# Sat_Cape_v9.net
KiCad netlist of a schematic drawn in EAGLE
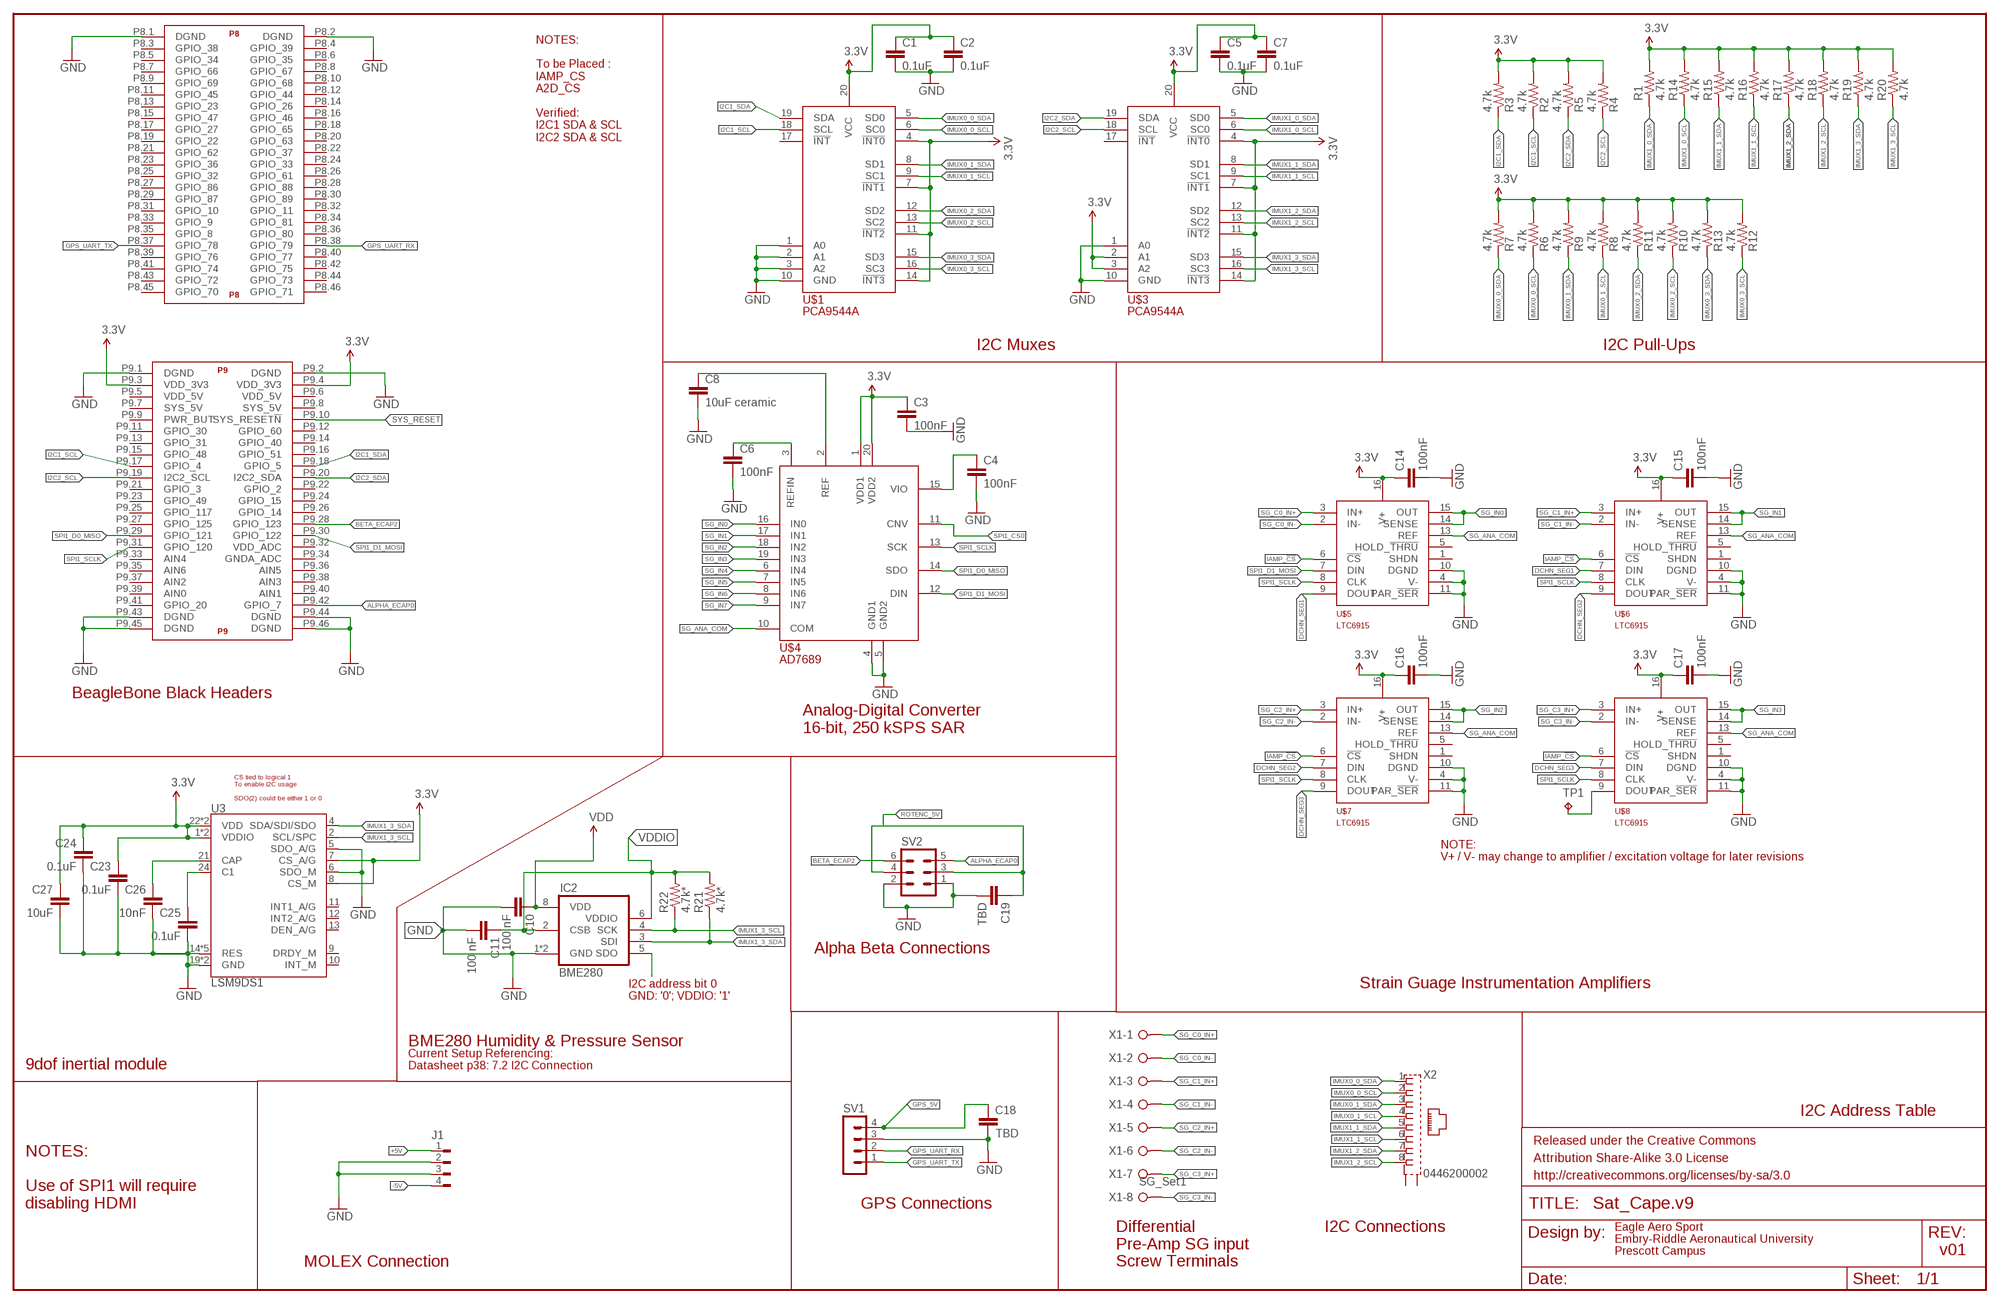
[diagram p0: schematic, sheet 1]

(export (version "E")
  (design (tool "Eeschema 10.0.6"))
  (components
    (comp (ref "C1")
      (value "0.1uF")
      (footprint "eagle-import:0805")
      (libsource (lib "eagle-import") (part "CAP0805"))
    )
    (comp (ref "C2")
      (value "0.1uF")
      (footprint "eagle-import:0805")
      (libsource (lib "eagle-import") (part "CAP0805"))
    )
    (comp (ref "C3")
      (value "100nF")
      (footprint "eagle-import:0805")
      (libsource (lib "eagle-import") (part "CAP0805"))
    )
    (comp (ref "C4")
      (value "100nF")
      (footprint "eagle-import:0805")
      (libsource (lib "eagle-import") (part "CAP0805"))
    )
    (comp (ref "C5")
      (value "0.1uF")
      (footprint "eagle-import:0805")
      (libsource (lib "eagle-import") (part "CAP0805"))
    )
    (comp (ref "C6")
      (value "100nF")
      (footprint "eagle-import:0805")
      (libsource (lib "eagle-import") (part "CAP0805"))
    )
    (comp (ref "C7")
      (value "0.1uF")
      (footprint "eagle-import:0805")
      (libsource (lib "eagle-import") (part "CAP0805"))
    )
    (comp (ref "C8")
      (value "10uF ceramic")
      (footprint "eagle-import:0805")
      (libsource (lib "eagle-import") (part "CAP0805"))
    )
    (comp (ref "C10")
      (value "100 nF")
      (footprint "eagle-import:0805")
      (libsource (lib "eagle-import") (part "CAP0805"))
    )
    (comp (ref "C11")
      (value "100 nF")
      (footprint "eagle-import:0805")
      (libsource (lib "eagle-import") (part "CAP0805"))
    )
    (comp (ref "C14")
      (value "100nF")
      (footprint "eagle-import:0805")
      (libsource (lib "eagle-import") (part "CAP0805"))
    )
    (comp (ref "C15")
      (value "100nF")
      (footprint "eagle-import:0805")
      (libsource (lib "eagle-import") (part "CAP0805"))
    )
    (comp (ref "C16")
      (value "100nF")
      (footprint "eagle-import:0805")
      (libsource (lib "eagle-import") (part "CAP0805"))
    )
    (comp (ref "C17")
      (value "100nF")
      (footprint "eagle-import:0805")
      (libsource (lib "eagle-import") (part "CAP0805"))
    )
    (comp (ref "C18")
      (value "TBD")
      (footprint "eagle-import:0805")
      (libsource (lib "eagle-import") (part "CAP0805"))
    )
    (comp (ref "C19")
      (value "TBD")
      (footprint "eagle-import:0805")
      (libsource (lib "eagle-import") (part "CAP0805"))
    )
    (comp (ref "C23")
      (value "0.1uF")
      (footprint "eagle-import:0805")
      (libsource (lib "eagle-import") (part "CAP0805"))
    )
    (comp (ref "C24")
      (value "0.1uF")
      (footprint "eagle-import:0805")
      (libsource (lib "eagle-import") (part "CAP0805"))
    )
    (comp (ref "C25")
      (value "0.1uF")
      (footprint "eagle-import:0805")
      (libsource (lib "eagle-import") (part "CAP0805"))
    )
    (comp (ref "C26")
      (value "10nF")
      (footprint "eagle-import:0805")
      (libsource (lib "eagle-import") (part "CAP0805"))
    )
    (comp (ref "C27")
      (value "10uF")
      (footprint "eagle-import:0805")
      (libsource (lib "eagle-import") (part "CAP0805"))
    )
    (comp (ref "FRAME1")
      (value "FRAME-LEDGER")
      (footprint "eagle-import:CREATIVE_COMMONS")
      (libsource (lib "eagle-import") (part "FRAME-LEDGER"))
    )
    (comp (ref "IC2")
      (value "BME280")
      (footprint "eagle-import:BME280")
      (libsource (lib "eagle-import") (part "BME280"))
    )
    (comp (ref "J1")
      (value "FLOPPY-4350211")
      (footprint "eagle-import:350211")
      (libsource (lib "eagle-import") (part "FLOPPY-4350211"))
    )
    (comp (ref "R1")
      (value "4.7k")
      (footprint "eagle-import:0805")
      (libsource (lib "eagle-import") (part "RESISTOR0805-RES"))
    )
    (comp (ref "R2")
      (value "4.7k")
      (footprint "eagle-import:0805")
      (libsource (lib "eagle-import") (part "RESISTOR0805-RES"))
    )
    (comp (ref "R3")
      (value "4.7k")
      (footprint "eagle-import:0805")
      (libsource (lib "eagle-import") (part "RESISTOR0805-RES"))
    )
    (comp (ref "R4")
      (value "4.7k")
      (footprint "eagle-import:0805")
      (libsource (lib "eagle-import") (part "RESISTOR0805-RES"))
    )
    (comp (ref "R5")
      (value "4.7k")
      (footprint "eagle-import:0805")
      (libsource (lib "eagle-import") (part "RESISTOR0805-RES"))
    )
    (comp (ref "R6")
      (value "4.7k")
      (footprint "eagle-import:0805")
      (libsource (lib "eagle-import") (part "RESISTOR0805-RES"))
    )
    (comp (ref "R7")
      (value "4.7k")
      (footprint "eagle-import:0805")
      (libsource (lib "eagle-import") (part "RESISTOR0805-RES"))
    )
    (comp (ref "R8")
      (value "4.7k")
      (footprint "eagle-import:0805")
      (libsource (lib "eagle-import") (part "RESISTOR0805-RES"))
    )
    (comp (ref "R9")
      (value "4.7k")
      (footprint "eagle-import:0805")
      (libsource (lib "eagle-import") (part "RESISTOR0805-RES"))
    )
    (comp (ref "R10")
      (value "4.7k")
      (footprint "eagle-import:0805")
      (libsource (lib "eagle-import") (part "RESISTOR0805-RES"))
    )
    (comp (ref "R11")
      (value "4.7k")
      (footprint "eagle-import:0805")
      (libsource (lib "eagle-import") (part "RESISTOR0805-RES"))
    )
    (comp (ref "R12")
      (value "4.7k")
      (footprint "eagle-import:0805")
      (libsource (lib "eagle-import") (part "RESISTOR0805-RES"))
    )
    (comp (ref "R13")
      (value "4.7k")
      (footprint "eagle-import:0805")
      (libsource (lib "eagle-import") (part "RESISTOR0805-RES"))
    )
    (comp (ref "R14")
      (value "4.7k")
      (footprint "eagle-import:0805")
      (libsource (lib "eagle-import") (part "RESISTOR0805-RES"))
    )
    (comp (ref "R15")
      (value "4.7k")
      (footprint "eagle-import:0805")
      (libsource (lib "eagle-import") (part "RESISTOR0805-RES"))
    )
    (comp (ref "R16")
      (value "4.7k")
      (footprint "eagle-import:0805")
      (libsource (lib "eagle-import") (part "RESISTOR0805-RES"))
    )
    (comp (ref "R17")
      (value "4.7k")
      (footprint "eagle-import:0805")
      (libsource (lib "eagle-import") (part "RESISTOR0805-RES"))
    )
    (comp (ref "R18")
      (value "4.7k")
      (footprint "eagle-import:0805")
      (libsource (lib "eagle-import") (part "RESISTOR0805-RES"))
    )
    (comp (ref "R19")
      (value "4.7k")
      (footprint "eagle-import:0805")
      (libsource (lib "eagle-import") (part "RESISTOR0805-RES"))
    )
    (comp (ref "R20")
      (value "4.7k")
      (footprint "eagle-import:0805")
      (libsource (lib "eagle-import") (part "RESISTOR0805-RES"))
    )
    (comp (ref "R21")
      (value "4.7k*")
      (footprint "eagle-import:0805")
      (libsource (lib "eagle-import") (part "RESISTOR0805-RES"))
    )
    (comp (ref "R22")
      (value "4.7k*")
      (footprint "eagle-import:0805")
      (libsource (lib "eagle-import") (part "RESISTOR0805-RES"))
    )
    (comp (ref "SV1")
      (value "MA04-1")
      (footprint "eagle-import:MA04-1")
      (libsource (lib "eagle-import") (part "MA04-1"))
    )
    (comp (ref "SV2")
      (value "MA03-2")
      (footprint "eagle-import:MA03-2")
      (libsource (lib "eagle-import") (part "MA03-2"))
    )
    (comp (ref "TP1")
      (value "TPTP08R")
      (footprint "eagle-import:TP08R")
      (libsource (lib "eagle-import") (part "TPTP08R"))
    )
    (comp (ref "U$1")
      (value "PCA9544A")
      (footprint "eagle-import:TSSOP20")
      (libsource (lib "eagle-import") (part "PCA9544A"))
    )
    (comp (ref "U$2")
      (value "BEAGLE_BONE_BLACK_CAPE")
      (footprint "eagle-import:BEAGLE_BONE_BLACK_CAPE")
      (libsource (lib "eagle-import") (part "BEAGLE_BONE_BLACK_CAPE"))
    )
    (comp (ref "U$3")
      (value "PCA9544A")
      (footprint "eagle-import:TSSOP20")
      (libsource (lib "eagle-import") (part "PCA9544A"))
    )
    (comp (ref "U$4")
      (value "AD7689")
      (footprint "eagle-import:QFN20")
      (libsource (lib "eagle-import") (part "AD7689"))
    )
    (comp (ref "U$5")
      (value "LTC6915")
      (footprint "eagle-import:SSOP16")
      (libsource (lib "eagle-import") (part "LTC6915"))
    )
    (comp (ref "U$6")
      (value "LTC6915")
      (footprint "eagle-import:SSOP16")
      (libsource (lib "eagle-import") (part "LTC6915"))
    )
    (comp (ref "U$7")
      (value "LTC6915")
      (footprint "eagle-import:SSOP16")
      (libsource (lib "eagle-import") (part "LTC6915"))
    )
    (comp (ref "U$8")
      (value "LTC6915")
      (footprint "eagle-import:SSOP16")
      (libsource (lib "eagle-import") (part "LTC6915"))
    )
    (comp (ref "U3")
      (value "LSM9DS1")
      (footprint "eagle-import:LGA24-8X4")
      (libsource (lib "eagle-import") (part "LSM9DS1"))
    )
    (comp (ref "X1")
      (value "SG_Set1")
      (footprint "eagle-import:W237-8P")
      (libsource (lib "eagle-import") (part "W237-08P"))
    )
    (comp (ref "X2")
      (value "0446200002")
      (footprint "eagle-import:0446200002")
      (fields (field (name "MF") "MOLEX"))
      (libsource (lib "eagle-import") (part "0446200002"))
    )
  )
  (nets
    (net (code "1") (name "+5V") (class "Default")
      (node (ref "J1") (pin "1") (pinfunction "1_1") (pintype "passive"))
    )
    (net (code "2") (name "-5V") (class "Default")
      (node (ref "J1") (pin "4") (pinfunction "4_4") (pintype "passive"))
    )
    (net (code "3") (name "/IAMP_~{CS}") (class "Default")
      (node (ref "U$5") (pin "6") (pinfunction "~{CS}_6") (pintype "bidirectional"))
      (node (ref "U$6") (pin "6") (pinfunction "~{CS}_6") (pintype "bidirectional"))
      (node (ref "U$7") (pin "6") (pinfunction "~{CS}_6") (pintype "bidirectional"))
      (node (ref "U$8") (pin "6") (pinfunction "~{CS}_6") (pintype "bidirectional"))
    )
    (net (code "4") (name "3.3V") (class "Default")
      (node (ref "C1") (pin "1") (pinfunction "1_1") (pintype "passive"))
      (node (ref "C14") (pin "1") (pinfunction "1_1") (pintype "passive"))
      (node (ref "C15") (pin "1") (pinfunction "1_1") (pintype "passive"))
      (node (ref "C16") (pin "1") (pinfunction "1_1") (pintype "passive"))
      (node (ref "C17") (pin "1") (pinfunction "1_1") (pintype "passive"))
      (node (ref "C2") (pin "1") (pinfunction "1_1") (pintype "passive"))
      (node (ref "C23") (pin "1") (pinfunction "1_1") (pintype "passive"))
      (node (ref "C24") (pin "1") (pinfunction "1_1") (pintype "passive"))
      (node (ref "C27") (pin "1") (pinfunction "1_1") (pintype "passive"))
      (node (ref "C3") (pin "1") (pinfunction "1_1") (pintype "passive"))
      (node (ref "C5") (pin "1") (pinfunction "1_1") (pintype "passive"))
      (node (ref "C7") (pin "1") (pinfunction "1_1") (pintype "passive"))
      (node (ref "R1") (pin "2") (pinfunction "2_2") (pintype "passive"))
      (node (ref "R10") (pin "2") (pinfunction "2_2") (pintype "passive"))
      (node (ref "R11") (pin "2") (pinfunction "2_2") (pintype "passive"))
      (node (ref "R12") (pin "2") (pinfunction "2_2") (pintype "passive"))
      (node (ref "R13") (pin "2") (pinfunction "2_2") (pintype "passive"))
      (node (ref "R14") (pin "2") (pinfunction "2_2") (pintype "passive"))
      (node (ref "R15") (pin "2") (pinfunction "2_2") (pintype "passive"))
      (node (ref "R16") (pin "2") (pinfunction "2_2") (pintype "passive"))
      (node (ref "R17") (pin "2") (pinfunction "2_2") (pintype "passive"))
      (node (ref "R18") (pin "2") (pinfunction "2_2") (pintype "passive"))
      (node (ref "R19") (pin "2") (pinfunction "2_2") (pintype "passive"))
      (node (ref "R2") (pin "2") (pinfunction "2_2") (pintype "passive"))
      (node (ref "R20") (pin "2") (pinfunction "2_2") (pintype "passive"))
      (node (ref "R3") (pin "2") (pinfunction "2_2") (pintype "passive"))
      (node (ref "R4") (pin "2") (pinfunction "2_2") (pintype "passive"))
      (node (ref "R5") (pin "2") (pinfunction "2_2") (pintype "passive"))
      (node (ref "R6") (pin "2") (pinfunction "2_2") (pintype "passive"))
      (node (ref "R7") (pin "2") (pinfunction "2_2") (pintype "passive"))
      (node (ref "R8") (pin "2") (pinfunction "2_2") (pintype "passive"))
      (node (ref "R9") (pin "2") (pinfunction "2_2") (pintype "passive"))
      (node (ref "U$1") (pin "11") (pinfunction "~{INT2}_11") (pintype "input"))
      (node (ref "U$1") (pin "14") (pinfunction "~{INT3}_14") (pintype "input"))
      (node (ref "U$1") (pin "20") (pinfunction "VCC_20") (pintype "power_in"))
      (node (ref "U$1") (pin "4") (pinfunction "~{INT0}_4") (pintype "input"))
      (node (ref "U$1") (pin "7") (pinfunction "~{INT1}_7") (pintype "input"))
      (node (ref "U$2") (pin "P9.3") (pinfunction "VDD_3V3_P9.3") (pintype "bidirectional"))
      (node (ref "U$2") (pin "P9.4") (pinfunction "VDD_3V3_P9.4") (pintype "bidirectional"))
      (node (ref "U$3") (pin "11") (pinfunction "~{INT2}_11") (pintype "input"))
      (node (ref "U$3") (pin "14") (pinfunction "~{INT3}_14") (pintype "input"))
      (node (ref "U$3") (pin "2") (pinfunction "A1_2") (pintype "input"))
      (node (ref "U$3") (pin "20") (pinfunction "VCC_20") (pintype "power_in"))
      (node (ref "U$3") (pin "3") (pinfunction "A2_3") (pintype "input"))
      (node (ref "U$3") (pin "4") (pinfunction "~{INT0}_4") (pintype "input"))
      (node (ref "U$3") (pin "7") (pinfunction "~{INT1}_7") (pintype "input"))
      (node (ref "U$4") (pin "1") (pinfunction "VDD1_1") (pintype "bidirectional"))
      (node (ref "U$4") (pin "20") (pinfunction "VDD2_20") (pintype "bidirectional"))
      (node (ref "U$5") (pin "16") (pinfunction "V+_16") (pintype "bidirectional"))
      (node (ref "U$6") (pin "16") (pinfunction "V+_16") (pintype "bidirectional"))
      (node (ref "U$7") (pin "16") (pinfunction "V+_16") (pintype "bidirectional"))
      (node (ref "U$8") (pin "16") (pinfunction "V+_16") (pintype "bidirectional"))
      (node (ref "U3") (pin "1") (pinfunction "VDDIO_1") (pintype "bidirectional"))
      (node (ref "U3") (pin "22") (pinfunction "VDD_22") (pintype "bidirectional"))
      (node (ref "U3") (pin "23") (pinfunction "VDD_23") (pintype "bidirectional"))
      (node (ref "U3") (pin "3") (pinfunction "VDDIO_3") (pintype "bidirectional"))
      (node (ref "U3") (pin "7") (pinfunction "CS_A/G_7") (pintype "bidirectional"))
      (node (ref "U3") (pin "8") (pinfunction "CS_M_8") (pintype "bidirectional"))
    )
    (net (code "5") (name "ALPHA_ECAP0") (class "Default")
      (node (ref "SV2") (pin "5") (pinfunction "5_5") (pintype "passive"))
      (node (ref "U$2") (pin "P9.42") (pinfunction "GPIO_7_P9.42") (pintype "bidirectional"))
    )
    (net (code "6") (name "BETA_ECAP2") (class "Default")
      (node (ref "SV2") (pin "6") (pinfunction "6_6") (pintype "passive"))
      (node (ref "U$2") (pin "P9.28") (pinfunction "GPIO_123_P9.28") (pintype "bidirectional"))
    )
    (net (code "7") (name "DCHN_SEG1") (class "Default")
      (node (ref "U$5") (pin "9") (pinfunction "DOUT_9") (pintype "bidirectional"))
      (node (ref "U$6") (pin "7") (pinfunction "DIN_7") (pintype "bidirectional"))
    )
    (net (code "8") (name "DCHN_SEG2") (class "Default")
      (node (ref "U$6") (pin "9") (pinfunction "DOUT_9") (pintype "bidirectional"))
      (node (ref "U$7") (pin "7") (pinfunction "DIN_7") (pintype "bidirectional"))
    )
    (net (code "9") (name "DCHN_SEG3") (class "Default")
      (node (ref "U$7") (pin "9") (pinfunction "DOUT_9") (pintype "bidirectional"))
      (node (ref "U$8") (pin "7") (pinfunction "DIN_7") (pintype "bidirectional"))
    )
    (net (code "10") (name "GND") (class "Default")
      (node (ref "C1") (pin "2") (pinfunction "2_2") (pintype "passive"))
      (node (ref "C10") (pin "2") (pinfunction "2_2") (pintype "passive"))
      (node (ref "C11") (pin "2") (pinfunction "2_2") (pintype "passive"))
      (node (ref "C14") (pin "2") (pinfunction "2_2") (pintype "passive"))
      (node (ref "C15") (pin "2") (pinfunction "2_2") (pintype "passive"))
      (node (ref "C16") (pin "2") (pinfunction "2_2") (pintype "passive"))
      (node (ref "C17") (pin "2") (pinfunction "2_2") (pintype "passive"))
      (node (ref "C18") (pin "2") (pinfunction "2_2") (pintype "passive"))
      (node (ref "C19") (pin "2") (pinfunction "2_2") (pintype "passive"))
      (node (ref "C2") (pin "2") (pinfunction "2_2") (pintype "passive"))
      (node (ref "C23") (pin "2") (pinfunction "2_2") (pintype "passive"))
      (node (ref "C24") (pin "2") (pinfunction "2_2") (pintype "passive"))
      (node (ref "C25") (pin "2") (pinfunction "2_2") (pintype "passive"))
      (node (ref "C26") (pin "2") (pinfunction "2_2") (pintype "passive"))
      (node (ref "C27") (pin "2") (pinfunction "2_2") (pintype "passive"))
      (node (ref "C3") (pin "2") (pinfunction "2_2") (pintype "passive"))
      (node (ref "C4") (pin "2") (pinfunction "2_2") (pintype "passive"))
      (node (ref "C5") (pin "2") (pinfunction "2_2") (pintype "passive"))
      (node (ref "C6") (pin "2") (pinfunction "2_2") (pintype "passive"))
      (node (ref "C7") (pin "2") (pinfunction "2_2") (pintype "passive"))
      (node (ref "C8") (pin "2") (pinfunction "2_2") (pintype "passive"))
      (node (ref "IC2") (pin "1") (pinfunction "GND_1") (pintype "power_in"))
      (node (ref "IC2") (pin "7") (pinfunction "GND_7") (pintype "power_in"))
      (node (ref "J1") (pin "2") (pinfunction "2_2") (pintype "passive"))
      (node (ref "J1") (pin "3") (pinfunction "3_3") (pintype "passive"))
      (node (ref "SV1") (pin "3") (pinfunction "3_3") (pintype "passive"))
      (node (ref "SV2") (pin "1") (pinfunction "1_1") (pintype "passive"))
      (node (ref "SV2") (pin "2") (pinfunction "2_2") (pintype "passive"))
      (node (ref "U$1") (pin "1") (pinfunction "A0_1") (pintype "input"))
      (node (ref "U$1") (pin "10") (pinfunction "GND_10") (pintype "power_in"))
      (node (ref "U$1") (pin "2") (pinfunction "A1_2") (pintype "input"))
      (node (ref "U$1") (pin "3") (pinfunction "A2_3") (pintype "input"))
      (node (ref "U$2") (pin "P8.1") (pinfunction "DGND_P8.1") (pintype "bidirectional"))
      (node (ref "U$2") (pin "P8.2") (pinfunction "DGND_P8.2") (pintype "bidirectional"))
      (node (ref "U$2") (pin "P9.1") (pinfunction "DGND_P9.1") (pintype "bidirectional"))
      (node (ref "U$2") (pin "P9.2") (pinfunction "DGND_P9.2") (pintype "bidirectional"))
      (node (ref "U$2") (pin "P9.43") (pinfunction "DGND_P9.43") (pintype "bidirectional"))
      (node (ref "U$2") (pin "P9.44") (pinfunction "DGND_P9.44") (pintype "bidirectional"))
      (node (ref "U$2") (pin "P9.45") (pinfunction "DGND_P9.45") (pintype "bidirectional"))
      (node (ref "U$2") (pin "P9.46") (pinfunction "DGND_P9.46") (pintype "bidirectional"))
      (node (ref "U$3") (pin "1") (pinfunction "A0_1") (pintype "input"))
      (node (ref "U$3") (pin "10") (pinfunction "GND_10") (pintype "power_in"))
      (node (ref "U$4") (pin "4") (pinfunction "GND1_4") (pintype "bidirectional"))
      (node (ref "U$4") (pin "5") (pinfunction "GND2_5") (pintype "bidirectional"))
      (node (ref "U$5") (pin "10") (pinfunction "DGND_10") (pintype "bidirectional"))
      (node (ref "U$5") (pin "11") (pinfunction "PAR_~{SER}_11") (pintype "bidirectional"))
      (node (ref "U$5") (pin "4") (pinfunction "V-_4") (pintype "bidirectional"))
      (node (ref "U$6") (pin "10") (pinfunction "DGND_10") (pintype "bidirectional"))
      (node (ref "U$6") (pin "11") (pinfunction "PAR_~{SER}_11") (pintype "bidirectional"))
      (node (ref "U$6") (pin "4") (pinfunction "V-_4") (pintype "bidirectional"))
      (node (ref "U$7") (pin "10") (pinfunction "DGND_10") (pintype "bidirectional"))
      (node (ref "U$7") (pin "11") (pinfunction "PAR_~{SER}_11") (pintype "bidirectional"))
      (node (ref "U$7") (pin "4") (pinfunction "V-_4") (pintype "bidirectional"))
      (node (ref "U$8") (pin "10") (pinfunction "DGND_10") (pintype "bidirectional"))
      (node (ref "U$8") (pin "11") (pinfunction "PAR_~{SER}_11") (pintype "bidirectional"))
      (node (ref "U$8") (pin "4") (pinfunction "V-_4") (pintype "bidirectional"))
      (node (ref "U3") (pin "14") (pinfunction "RES_14") (pintype "bidirectional"))
      (node (ref "U3") (pin "15") (pinfunction "RES_15") (pintype "bidirectional"))
      (node (ref "U3") (pin "16") (pinfunction "RES_16") (pintype "bidirectional"))
      (node (ref "U3") (pin "17") (pinfunction "RES_17") (pintype "bidirectional"))
      (node (ref "U3") (pin "18") (pinfunction "RES_18") (pintype "bidirectional"))
      (node (ref "U3") (pin "19") (pinfunction "GND_19") (pintype "bidirectional"))
      (node (ref "U3") (pin "20") (pinfunction "GND_20") (pintype "bidirectional"))
      (node (ref "U3") (pin "5") (pinfunction "SDO_A/G_5") (pintype "bidirectional"))
      (node (ref "U3") (pin "6") (pinfunction "SDO_M_6") (pintype "bidirectional"))
    )
    (net (code "11") (name "GPS_5V") (class "Default")
      (node (ref "C18") (pin "1") (pinfunction "1_1") (pintype "passive"))
      (node (ref "SV1") (pin "4") (pinfunction "4_4") (pintype "passive"))
    )
    (net (code "12") (name "GPS_UART_RX") (class "Default")
      (node (ref "SV1") (pin "2") (pinfunction "2_2") (pintype "passive"))
      (node (ref "U$2") (pin "P8.38") (pinfunction "GPIO_79_P8.38") (pintype "bidirectional"))
    )
    (net (code "13") (name "GPS_UART_TX") (class "Default")
      (node (ref "SV1") (pin "1") (pinfunction "1_1") (pintype "passive"))
      (node (ref "U$2") (pin "P8.37") (pinfunction "GPIO_78_P8.37") (pintype "bidirectional"))
    )
    (net (code "14") (name "I2C1_SCL") (class "Default")
      (node (ref "R2") (pin "1") (pinfunction "1_1") (pintype "passive"))
      (node (ref "U$1") (pin "18") (pinfunction "SCL_18") (pintype "input"))
      (node (ref "U$2") (pin "P9.17") (pinfunction "GPIO_4_P9.17") (pintype "bidirectional"))
    )
    (net (code "15") (name "I2C1_SDA") (class "Default")
      (node (ref "R3") (pin "1") (pinfunction "1_1") (pintype "passive"))
      (node (ref "U$1") (pin "19") (pinfunction "SDA_19") (pintype "bidirectional"))
      (node (ref "U$2") (pin "P9.18") (pinfunction "GPIO_5_P9.18") (pintype "bidirectional"))
    )
    (net (code "16") (name "I2C2_SCL") (class "Default")
      (node (ref "R4") (pin "1") (pinfunction "1_1") (pintype "passive"))
      (node (ref "U$2") (pin "P9.19") (pinfunction "I2C2_SCL_P9.19") (pintype "bidirectional"))
      (node (ref "U$3") (pin "18") (pinfunction "SCL_18") (pintype "input"))
    )
    (net (code "17") (name "I2C2_SDA") (class "Default")
      (node (ref "R5") (pin "1") (pinfunction "1_1") (pintype "passive"))
      (node (ref "U$2") (pin "P9.20") (pinfunction "I2C2_SDA_P9.20") (pintype "bidirectional"))
      (node (ref "U$3") (pin "19") (pinfunction "SDA_19") (pintype "bidirectional"))
    )
    (net (code "18") (name "IMUX0_0_SCL") (class "Default")
      (node (ref "R6") (pin "1") (pinfunction "1_1") (pintype "passive"))
      (node (ref "U$1") (pin "6") (pinfunction "SC0_6") (pintype "output"))
      (node (ref "X2") (pin "2") (pinfunction "2_2") (pintype "passive"))
    )
    (net (code "19") (name "IMUX0_0_SDA") (class "Default")
      (node (ref "R7") (pin "1") (pinfunction "1_1") (pintype "passive"))
      (node (ref "U$1") (pin "5") (pinfunction "SD0_5") (pintype "bidirectional"))
      (node (ref "X2") (pin "1") (pinfunction "1_1") (pintype "passive"))
    )
    (net (code "20") (name "IMUX0_1_SCL") (class "Default")
      (node (ref "R8") (pin "1") (pinfunction "1_1") (pintype "passive"))
      (node (ref "U$1") (pin "9") (pinfunction "SC1_9") (pintype "output"))
      (node (ref "X2") (pin "4") (pinfunction "4_4") (pintype "passive"))
    )
    (net (code "21") (name "IMUX0_1_SDA") (class "Default")
      (node (ref "R9") (pin "1") (pinfunction "1_1") (pintype "passive"))
      (node (ref "U$1") (pin "8") (pinfunction "SD1_8") (pintype "bidirectional"))
      (node (ref "X2") (pin "3") (pinfunction "3_3") (pintype "passive"))
    )
    (net (code "22") (name "IMUX0_2_SCL") (class "Default")
      (node (ref "R10") (pin "1") (pinfunction "1_1") (pintype "passive"))
      (node (ref "U$1") (pin "13") (pinfunction "SC2_13") (pintype "output"))
    )
    (net (code "23") (name "IMUX0_2_SDA") (class "Default")
      (node (ref "R11") (pin "1") (pinfunction "1_1") (pintype "passive"))
      (node (ref "U$1") (pin "12") (pinfunction "SD2_12") (pintype "bidirectional"))
    )
    (net (code "24") (name "IMUX0_3_SCL") (class "Default")
      (node (ref "R12") (pin "1") (pinfunction "1_1") (pintype "passive"))
      (node (ref "U$1") (pin "16") (pinfunction "SC3_16") (pintype "output"))
    )
    (net (code "25") (name "IMUX0_3_SDA") (class "Default")
      (node (ref "R13") (pin "1") (pinfunction "1_1") (pintype "passive"))
      (node (ref "U$1") (pin "15") (pinfunction "SD3_15") (pintype "bidirectional"))
    )
    (net (code "26") (name "IMUX1_0_SCL") (class "Default")
      (node (ref "R14") (pin "1") (pinfunction "1_1") (pintype "passive"))
      (node (ref "U$3") (pin "6") (pinfunction "SC0_6") (pintype "output"))
    )
    (net (code "27") (name "IMUX1_0_SDA") (class "Default")
      (node (ref "R1") (pin "1") (pinfunction "1_1") (pintype "passive"))
      (node (ref "U$3") (pin "5") (pinfunction "SD0_5") (pintype "bidirectional"))
    )
    (net (code "28") (name "IMUX1_1_SCL") (class "Default")
      (node (ref "R16") (pin "1") (pinfunction "1_1") (pintype "passive"))
      (node (ref "U$3") (pin "9") (pinfunction "SC1_9") (pintype "output"))
      (node (ref "X2") (pin "6") (pinfunction "6_6") (pintype "passive"))
    )
    (net (code "29") (name "IMUX1_1_SDA") (class "Default")
      (node (ref "R15") (pin "1") (pinfunction "1_1") (pintype "passive"))
      (node (ref "U$3") (pin "8") (pinfunction "SD1_8") (pintype "bidirectional"))
      (node (ref "X2") (pin "5") (pinfunction "5_5") (pintype "passive"))
    )
    (net (code "30") (name "IMUX1_2_SCL") (class "Default")
      (node (ref "R18") (pin "1") (pinfunction "1_1") (pintype "passive"))
      (node (ref "U$3") (pin "13") (pinfunction "SC2_13") (pintype "output"))
      (node (ref "X2") (pin "8") (pinfunction "8_8") (pintype "passive"))
    )
    (net (code "31") (name "IMUX1_2_SDA") (class "Default")
      (node (ref "R17") (pin "1") (pinfunction "1_1") (pintype "passive"))
      (node (ref "U$3") (pin "12") (pinfunction "SD2_12") (pintype "bidirectional"))
      (node (ref "X2") (pin "7") (pinfunction "7_7") (pintype "passive"))
    )
    (net (code "32") (name "IMUX1_3_SCL") (class "Default")
      (node (ref "IC2") (pin "4") (pinfunction "SCK_4") (pintype "bidirectional"))
      (node (ref "R20") (pin "1") (pinfunction "1_1") (pintype "passive"))
      (node (ref "R22") (pin "1") (pinfunction "1_1") (pintype "passive"))
      (node (ref "U$3") (pin "16") (pinfunction "SC3_16") (pintype "output"))
      (node (ref "U3") (pin "2") (pinfunction "SCL/SPC_2") (pintype "bidirectional"))
    )
    (net (code "33") (name "IMUX1_3_SDA") (class "Default")
      (node (ref "IC2") (pin "3") (pinfunction "SDI_3") (pintype "bidirectional"))
      (node (ref "R19") (pin "1") (pinfunction "1_1") (pintype "passive"))
      (node (ref "R21") (pin "1") (pinfunction "1_1") (pintype "passive"))
      (node (ref "U$3") (pin "15") (pinfunction "SD3_15") (pintype "bidirectional"))
      (node (ref "U3") (pin "4") (pinfunction "SDA/SDI/SDO_4") (pintype "bidirectional"))
    )
    (net (code "34") (name "Net-(U$4-REF)") (class "Default")
      (node (ref "C8") (pin "1") (pinfunction "1_1") (pintype "passive"))
      (node (ref "U$4") (pin "2") (pinfunction "REF_2") (pintype "bidirectional"))
    )
    (net (code "35") (name "Net-(U$4-REFIN)") (class "Default")
      (node (ref "C6") (pin "1") (pinfunction "1_1") (pintype "passive"))
      (node (ref "U$4") (pin "3") (pinfunction "REFIN_3") (pintype "bidirectional"))
    )
    (net (code "36") (name "Net-(U$4-VIO)") (class "Default")
      (node (ref "C4") (pin "1") (pinfunction "1_1") (pintype "passive"))
      (node (ref "U$4") (pin "15") (pinfunction "VIO_15") (pintype "bidirectional"))
    )
    (net (code "37") (name "Net-(U$8-DOUT)") (class "Default")
      (node (ref "TP1") (pin "TP") (pinfunction "TP_TP") (pintype "input"))
      (node (ref "U$8") (pin "9") (pinfunction "DOUT_9") (pintype "bidirectional"))
    )
    (net (code "38") (name "Net-(U3-C1)") (class "Default")
      (node (ref "C25") (pin "1") (pinfunction "1_1") (pintype "passive"))
      (node (ref "U3") (pin "24") (pinfunction "C1_24") (pintype "bidirectional"))
    )
    (net (code "39") (name "Net-(U3-CAP)") (class "Default")
      (node (ref "C26") (pin "1") (pinfunction "1_1") (pintype "passive"))
      (node (ref "U3") (pin "21") (pinfunction "CAP_21") (pintype "bidirectional"))
    )
    (net (code "40") (name "ROTENC_5V") (class "Default")
      (node (ref "C19") (pin "1") (pinfunction "1_1") (pintype "passive"))
      (node (ref "SV2") (pin "3") (pinfunction "3_3") (pintype "passive"))
      (node (ref "SV2") (pin "4") (pinfunction "4_4") (pintype "passive"))
    )
    (net (code "41") (name "SG_ANA_COM") (class "Default")
      (node (ref "U$4") (pin "10") (pinfunction "COM_10") (pintype "bidirectional"))
      (node (ref "U$5") (pin "13") (pinfunction "REF_13") (pintype "bidirectional"))
      (node (ref "U$6") (pin "13") (pinfunction "REF_13") (pintype "bidirectional"))
      (node (ref "U$7") (pin "13") (pinfunction "REF_13") (pintype "bidirectional"))
      (node (ref "U$8") (pin "13") (pinfunction "REF_13") (pintype "bidirectional"))
    )
    (net (code "42") (name "SG_C0_IN+") (class "Default")
      (node (ref "U$5") (pin "3") (pinfunction "IN+_3") (pintype "bidirectional"))
      (node (ref "X1") (pin "1") (pinfunction "KL_1") (pintype "passive"))
    )
    (net (code "43") (name "SG_C0_IN-") (class "Default")
      (node (ref "U$5") (pin "2") (pinfunction "IN-_2") (pintype "bidirectional"))
      (node (ref "X1") (pin "2") (pinfunction "KL_2") (pintype "passive"))
    )
    (net (code "44") (name "SG_C1_IN+") (class "Default")
      (node (ref "U$6") (pin "3") (pinfunction "IN+_3") (pintype "bidirectional"))
      (node (ref "X1") (pin "3") (pinfunction "KL_3") (pintype "passive"))
    )
    (net (code "45") (name "SG_C1_IN-") (class "Default")
      (node (ref "U$6") (pin "2") (pinfunction "IN-_2") (pintype "bidirectional"))
      (node (ref "X1") (pin "4") (pinfunction "KL_4") (pintype "passive"))
    )
    (net (code "46") (name "SG_C2_IN+") (class "Default")
      (node (ref "U$7") (pin "3") (pinfunction "IN+_3") (pintype "bidirectional"))
      (node (ref "X1") (pin "5") (pinfunction "KL_5") (pintype "passive"))
    )
    (net (code "47") (name "SG_C2_IN-") (class "Default")
      (node (ref "U$7") (pin "2") (pinfunction "IN-_2") (pintype "bidirectional"))
      (node (ref "X1") (pin "6") (pinfunction "KL_6") (pintype "passive"))
    )
    (net (code "48") (name "SG_C3_IN+") (class "Default")
      (node (ref "U$8") (pin "3") (pinfunction "IN+_3") (pintype "bidirectional"))
      (node (ref "X1") (pin "7") (pinfunction "KL_7") (pintype "passive"))
    )
    (net (code "49") (name "SG_C3_IN-") (class "Default")
      (node (ref "U$8") (pin "2") (pinfunction "IN-_2") (pintype "bidirectional"))
      (node (ref "X1") (pin "8") (pinfunction "KL_8") (pintype "passive"))
    )
    (net (code "50") (name "SG_IN0") (class "Default")
      (node (ref "U$4") (pin "16") (pinfunction "IN0_16") (pintype "bidirectional"))
      (node (ref "U$5") (pin "14") (pinfunction "SENSE_14") (pintype "bidirectional"))
      (node (ref "U$5") (pin "15") (pinfunction "OUT_15") (pintype "bidirectional"))
    )
    (net (code "51") (name "SG_IN1") (class "Default")
      (node (ref "U$4") (pin "17") (pinfunction "IN1_17") (pintype "bidirectional"))
      (node (ref "U$6") (pin "14") (pinfunction "SENSE_14") (pintype "bidirectional"))
      (node (ref "U$6") (pin "15") (pinfunction "OUT_15") (pintype "bidirectional"))
    )
    (net (code "52") (name "SG_IN2") (class "Default")
      (node (ref "U$4") (pin "18") (pinfunction "IN2_18") (pintype "bidirectional"))
      (node (ref "U$7") (pin "14") (pinfunction "SENSE_14") (pintype "bidirectional"))
      (node (ref "U$7") (pin "15") (pinfunction "OUT_15") (pintype "bidirectional"))
    )
    (net (code "53") (name "SG_IN3") (class "Default")
      (node (ref "U$4") (pin "19") (pinfunction "IN3_19") (pintype "bidirectional"))
      (node (ref "U$8") (pin "14") (pinfunction "SENSE_14") (pintype "bidirectional"))
      (node (ref "U$8") (pin "15") (pinfunction "OUT_15") (pintype "bidirectional"))
    )
    (net (code "54") (name "SG_IN4") (class "Default")
      (node (ref "U$4") (pin "6") (pinfunction "IN4_6") (pintype "bidirectional"))
    )
    (net (code "55") (name "SG_IN5") (class "Default")
      (node (ref "U$4") (pin "7") (pinfunction "IN5_7") (pintype "bidirectional"))
    )
    (net (code "56") (name "SG_IN6") (class "Default")
      (node (ref "U$4") (pin "8") (pinfunction "IN6_8") (pintype "bidirectional"))
    )
    (net (code "57") (name "SG_IN7") (class "Default")
      (node (ref "U$4") (pin "9") (pinfunction "IN7_9") (pintype "bidirectional"))
    )
    (net (code "58") (name "SPI1_CS0") (class "Default")
      (node (ref "U$4") (pin "11") (pinfunction "CNV_11") (pintype "bidirectional"))
    )
    (net (code "59") (name "SPI1_D0_MISO") (class "Default")
      (node (ref "U$2") (pin "P9.29") (pinfunction "GPIO_121_P9.29") (pintype "bidirectional"))
      (node (ref "U$4") (pin "14") (pinfunction "SDO_14") (pintype "bidirectional"))
    )
    (net (code "60") (name "SPI1_D1_MOSI") (class "Default")
      (node (ref "U$2") (pin "P9.30") (pinfunction "GPIO_122_P9.30") (pintype "bidirectional"))
      (node (ref "U$4") (pin "12") (pinfunction "DIN_12") (pintype "bidirectional"))
      (node (ref "U$5") (pin "7") (pinfunction "DIN_7") (pintype "bidirectional"))
    )
    (net (code "61") (name "SPI1_SCLK") (class "Default")
      (node (ref "U$2") (pin "P9.31") (pinfunction "GPIO_120_P9.31") (pintype "bidirectional"))
      (node (ref "U$4") (pin "13") (pinfunction "SCK_13") (pintype "bidirectional"))
      (node (ref "U$5") (pin "8") (pinfunction "CLK_8") (pintype "bidirectional"))
      (node (ref "U$6") (pin "8") (pinfunction "CLK_8") (pintype "bidirectional"))
      (node (ref "U$7") (pin "8") (pinfunction "CLK_8") (pintype "bidirectional"))
      (node (ref "U$8") (pin "8") (pinfunction "CLK_8") (pintype "bidirectional"))
    )
    (net (code "62") (name "SYS_RESET") (class "Default")
      (node (ref "U$2") (pin "P9.10") (pinfunction "SYS_RESET~{N}_P9.10") (pintype "bidirectional"))
    )
    (net (code "63") (name "VDD") (class "Default")
      (node (ref "C10") (pin "1") (pinfunction "1_1") (pintype "passive"))
      (node (ref "IC2") (pin "8") (pinfunction "VDD_8") (pintype "power_in"))
    )
    (net (code "64") (name "VDDIO") (class "Default")
      (node (ref "C11") (pin "1") (pinfunction "1_1") (pintype "passive"))
      (node (ref "IC2") (pin "2") (pinfunction "CSB_2") (pintype "input"))
      (node (ref "IC2") (pin "6") (pinfunction "VDDIO_6") (pintype "power_in"))
      (node (ref "R21") (pin "2") (pinfunction "2_2") (pintype "passive"))
      (node (ref "R22") (pin "2") (pinfunction "2_2") (pintype "passive"))
    )
    (net (code "65") (name "unconnected-(IC2-SDO-Pad5)") (class "Default")
      (node (ref "IC2") (pin "5") (pinfunction "SDO_5") (pintype "input"))
    )
    (net (code "66") (name "unconnected-(U$1-~{INT}-Pad17)") (class "Default")
      (node (ref "U$1") (pin "17") (pinfunction "~{INT}_17") (pintype "output"))
    )
    (net (code "67") (name "unconnected-(U$2A-GPIO_8-PadP8.35)") (class "Default")
      (node (ref "U$2") (pin "P8.35") (pinfunction "GPIO_8_P8.35") (pintype "bidirectional"))
    )
    (net (code "68") (name "unconnected-(U$2A-GPIO_9-PadP8.33)") (class "Default")
      (node (ref "U$2") (pin "P8.33") (pinfunction "GPIO_9_P8.33") (pintype "bidirectional"))
    )
    (net (code "69") (name "unconnected-(U$2A-GPIO_10-PadP8.31)") (class "Default")
      (node (ref "U$2") (pin "P8.31") (pinfunction "GPIO_10_P8.31") (pintype "bidirectional"))
    )
    (net (code "70") (name "unconnected-(U$2A-GPIO_11-PadP8.32)") (class "Default")
      (node (ref "U$2") (pin "P8.32") (pinfunction "GPIO_11_P8.32") (pintype "bidirectional"))
    )
    (net (code "71") (name "unconnected-(U$2A-GPIO_22-PadP8.19)") (class "Default")
      (node (ref "U$2") (pin "P8.19") (pinfunction "GPIO_22_P8.19") (pintype "bidirectional"))
    )
    (net (code "72") (name "unconnected-(U$2A-GPIO_23-PadP8.13)") (class "Default")
      (node (ref "U$2") (pin "P8.13") (pinfunction "GPIO_23_P8.13") (pintype "bidirectional"))
    )
    (net (code "73") (name "unconnected-(U$2A-GPIO_26-PadP8.14)") (class "Default")
      (node (ref "U$2") (pin "P8.14") (pinfunction "GPIO_26_P8.14") (pintype "bidirectional"))
    )
    (net (code "74") (name "unconnected-(U$2A-GPIO_27-PadP8.17)") (class "Default")
      (node (ref "U$2") (pin "P8.17") (pinfunction "GPIO_27_P8.17") (pintype "bidirectional"))
    )
    (net (code "75") (name "unconnected-(U$2A-GPIO_32-PadP8.25)") (class "Default")
      (node (ref "U$2") (pin "P8.25") (pinfunction "GPIO_32_P8.25") (pintype "bidirectional"))
    )
    (net (code "76") (name "unconnected-(U$2A-GPIO_33-PadP8.24)") (class "Default")
      (node (ref "U$2") (pin "P8.24") (pinfunction "GPIO_33_P8.24") (pintype "bidirectional"))
    )
    (net (code "77") (name "unconnected-(U$2A-GPIO_34-PadP8.5)") (class "Default")
      (node (ref "U$2") (pin "P8.5") (pinfunction "GPIO_34_P8.5") (pintype "bidirectional"))
    )
    (net (code "78") (name "unconnected-(U$2A-GPIO_35-PadP8.6)") (class "Default")
      (node (ref "U$2") (pin "P8.6") (pinfunction "GPIO_35_P8.6") (pintype "bidirectional"))
    )
    (net (code "79") (name "unconnected-(U$2A-GPIO_36-PadP8.23)") (class "Default")
      (node (ref "U$2") (pin "P8.23") (pinfunction "GPIO_36_P8.23") (pintype "bidirectional"))
    )
    (net (code "80") (name "unconnected-(U$2A-GPIO_37-PadP8.22)") (class "Default")
      (node (ref "U$2") (pin "P8.22") (pinfunction "GPIO_37_P8.22") (pintype "bidirectional"))
    )
    (net (code "81") (name "unconnected-(U$2A-GPIO_38-PadP8.3)") (class "Default")
      (node (ref "U$2") (pin "P8.3") (pinfunction "GPIO_38_P8.3") (pintype "bidirectional"))
    )
    (net (code "82") (name "unconnected-(U$2A-GPIO_39-PadP8.4)") (class "Default")
      (node (ref "U$2") (pin "P8.4") (pinfunction "GPIO_39_P8.4") (pintype "bidirectional"))
    )
    (net (code "83") (name "unconnected-(U$2A-GPIO_44-PadP8.12)") (class "Default")
      (node (ref "U$2") (pin "P8.12") (pinfunction "GPIO_44_P8.12") (pintype "bidirectional"))
    )
    (net (code "84") (name "unconnected-(U$2A-GPIO_45-PadP8.11)") (class "Default")
      (node (ref "U$2") (pin "P8.11") (pinfunction "GPIO_45_P8.11") (pintype "bidirectional"))
    )
    (net (code "85") (name "unconnected-(U$2A-GPIO_46-PadP8.16)") (class "Default")
      (node (ref "U$2") (pin "P8.16") (pinfunction "GPIO_46_P8.16") (pintype "bidirectional"))
    )
    (net (code "86") (name "unconnected-(U$2A-GPIO_47-PadP8.15)") (class "Default")
      (node (ref "U$2") (pin "P8.15") (pinfunction "GPIO_47_P8.15") (pintype "bidirectional"))
    )
    (net (code "87") (name "unconnected-(U$2A-GPIO_61-PadP8.26)") (class "Default")
      (node (ref "U$2") (pin "P8.26") (pinfunction "GPIO_61_P8.26") (pintype "bidirectional"))
    )
    (net (code "88") (name "unconnected-(U$2A-GPIO_62-PadP8.21)") (class "Default")
      (node (ref "U$2") (pin "P8.21") (pinfunction "GPIO_62_P8.21") (pintype "bidirectional"))
    )
    (net (code "89") (name "unconnected-(U$2A-GPIO_63-PadP8.20)") (class "Default")
      (node (ref "U$2") (pin "P8.20") (pinfunction "GPIO_63_P8.20") (pintype "bidirectional"))
    )
    (net (code "90") (name "unconnected-(U$2A-GPIO_65-PadP8.18)") (class "Default")
      (node (ref "U$2") (pin "P8.18") (pinfunction "GPIO_65_P8.18") (pintype "bidirectional"))
    )
    (net (code "91") (name "unconnected-(U$2A-GPIO_66-PadP8.7)") (class "Default")
      (node (ref "U$2") (pin "P8.7") (pinfunction "GPIO_66_P8.7") (pintype "bidirectional"))
    )
    (net (code "92") (name "unconnected-(U$2A-GPIO_67-PadP8.8)") (class "Default")
      (node (ref "U$2") (pin "P8.8") (pinfunction "GPIO_67_P8.8") (pintype "bidirectional"))
    )
    (net (code "93") (name "unconnected-(U$2A-GPIO_68-PadP8.10)") (class "Default")
      (node (ref "U$2") (pin "P8.10") (pinfunction "GPIO_68_P8.10") (pintype "bidirectional"))
    )
    (net (code "94") (name "unconnected-(U$2A-GPIO_69-PadP8.9)") (class "Default")
      (node (ref "U$2") (pin "P8.9") (pinfunction "GPIO_69_P8.9") (pintype "bidirectional"))
    )
    (net (code "95") (name "unconnected-(U$2A-GPIO_70-PadP8.45)") (class "Default")
      (node (ref "U$2") (pin "P8.45") (pinfunction "GPIO_70_P8.45") (pintype "bidirectional"))
    )
    (net (code "96") (name "unconnected-(U$2A-GPIO_71-PadP8.46)") (class "Default")
      (node (ref "U$2") (pin "P8.46") (pinfunction "GPIO_71_P8.46") (pintype "bidirectional"))
    )
    (net (code "97") (name "unconnected-(U$2A-GPIO_72-PadP8.43)") (class "Default")
      (node (ref "U$2") (pin "P8.43") (pinfunction "GPIO_72_P8.43") (pintype "bidirectional"))
    )
    (net (code "98") (name "unconnected-(U$2A-GPIO_73-PadP8.44)") (class "Default")
      (node (ref "U$2") (pin "P8.44") (pinfunction "GPIO_73_P8.44") (pintype "bidirectional"))
    )
    (net (code "99") (name "unconnected-(U$2A-GPIO_74-PadP8.41)") (class "Default")
      (node (ref "U$2") (pin "P8.41") (pinfunction "GPIO_74_P8.41") (pintype "bidirectional"))
    )
    (net (code "100") (name "unconnected-(U$2A-GPIO_75-PadP8.42)") (class "Default")
      (node (ref "U$2") (pin "P8.42") (pinfunction "GPIO_75_P8.42") (pintype "bidirectional"))
    )
    (net (code "101") (name "unconnected-(U$2A-GPIO_76-PadP8.39)") (class "Default")
      (node (ref "U$2") (pin "P8.39") (pinfunction "GPIO_76_P8.39") (pintype "bidirectional"))
    )
    (net (code "102") (name "unconnected-(U$2A-GPIO_77-PadP8.40)") (class "Default")
      (node (ref "U$2") (pin "P8.40") (pinfunction "GPIO_77_P8.40") (pintype "bidirectional"))
    )
    (net (code "103") (name "unconnected-(U$2A-GPIO_80-PadP8.36)") (class "Default")
      (node (ref "U$2") (pin "P8.36") (pinfunction "GPIO_80_P8.36") (pintype "bidirectional"))
    )
    (net (code "104") (name "unconnected-(U$2A-GPIO_81-PadP8.34)") (class "Default")
      (node (ref "U$2") (pin "P8.34") (pinfunction "GPIO_81_P8.34") (pintype "bidirectional"))
    )
    (net (code "105") (name "unconnected-(U$2A-GPIO_86-PadP8.27)") (class "Default")
      (node (ref "U$2") (pin "P8.27") (pinfunction "GPIO_86_P8.27") (pintype "bidirectional"))
    )
    (net (code "106") (name "unconnected-(U$2A-GPIO_87-PadP8.29)") (class "Default")
      (node (ref "U$2") (pin "P8.29") (pinfunction "GPIO_87_P8.29") (pintype "bidirectional"))
    )
    (net (code "107") (name "unconnected-(U$2A-GPIO_88-PadP8.28)") (class "Default")
      (node (ref "U$2") (pin "P8.28") (pinfunction "GPIO_88_P8.28") (pintype "bidirectional"))
    )
    (net (code "108") (name "unconnected-(U$2A-GPIO_89-PadP8.30)") (class "Default")
      (node (ref "U$2") (pin "P8.30") (pinfunction "GPIO_89_P8.30") (pintype "bidirectional"))
    )
    (net (code "109") (name "unconnected-(U$2B-AIN0-PadP9.39)") (class "Default")
      (node (ref "U$2") (pin "P9.39") (pinfunction "AIN0_P9.39") (pintype "bidirectional"))
    )
    (net (code "110") (name "unconnected-(U$2B-AIN1-PadP9.40)") (class "Default")
      (node (ref "U$2") (pin "P9.40") (pinfunction "AIN1_P9.40") (pintype "bidirectional"))
    )
    (net (code "111") (name "unconnected-(U$2B-AIN2-PadP9.37)") (class "Default")
      (node (ref "U$2") (pin "P9.37") (pinfunction "AIN2_P9.37") (pintype "bidirectional"))
    )
    (net (code "112") (name "unconnected-(U$2B-AIN3-PadP9.38)") (class "Default")
      (node (ref "U$2") (pin "P9.38") (pinfunction "AIN3_P9.38") (pintype "bidirectional"))
    )
    (net (code "113") (name "unconnected-(U$2B-AIN4-PadP9.33)") (class "Default")
      (node (ref "U$2") (pin "P9.33") (pinfunction "AIN4_P9.33") (pintype "bidirectional"))
    )
    (net (code "114") (name "unconnected-(U$2B-AIN5-PadP9.36)") (class "Default")
      (node (ref "U$2") (pin "P9.36") (pinfunction "AIN5_P9.36") (pintype "bidirectional"))
    )
    (net (code "115") (name "unconnected-(U$2B-AIN6-PadP9.35)") (class "Default")
      (node (ref "U$2") (pin "P9.35") (pinfunction "AIN6_P9.35") (pintype "bidirectional"))
    )
    (net (code "116") (name "unconnected-(U$2B-GNDA_ADC-PadP9.34)") (class "Default")
      (node (ref "U$2") (pin "P9.34") (pinfunction "GNDA_ADC_P9.34") (pintype "bidirectional"))
    )
    (net (code "117") (name "unconnected-(U$2B-GPIO_2-PadP9.22)") (class "Default")
      (node (ref "U$2") (pin "P9.22") (pinfunction "GPIO_2_P9.22") (pintype "bidirectional"))
    )
    (net (code "118") (name "unconnected-(U$2B-GPIO_3-PadP9.21)") (class "Default")
      (node (ref "U$2") (pin "P9.21") (pinfunction "GPIO_3_P9.21") (pintype "bidirectional"))
    )
    (net (code "119") (name "unconnected-(U$2B-GPIO_14-PadP9.26)") (class "Default")
      (node (ref "U$2") (pin "P9.26") (pinfunction "GPIO_14_P9.26") (pintype "bidirectional"))
    )
    (net (code "120") (name "unconnected-(U$2B-GPIO_15-PadP9.24)") (class "Default")
      (node (ref "U$2") (pin "P9.24") (pinfunction "GPIO_15_P9.24") (pintype "bidirectional"))
    )
    (net (code "121") (name "unconnected-(U$2B-GPIO_20-PadP9.41)") (class "Default")
      (node (ref "U$2") (pin "P9.41") (pinfunction "GPIO_20_P9.41") (pintype "bidirectional"))
    )
    (net (code "122") (name "unconnected-(U$2B-GPIO_30-PadP9.11)") (class "Default")
      (node (ref "U$2") (pin "P9.11") (pinfunction "GPIO_30_P9.11") (pintype "bidirectional"))
    )
    (net (code "123") (name "unconnected-(U$2B-GPIO_31-PadP9.13)") (class "Default")
      (node (ref "U$2") (pin "P9.13") (pinfunction "GPIO_31_P9.13") (pintype "bidirectional"))
    )
    (net (code "124") (name "unconnected-(U$2B-GPIO_40-PadP9.14)") (class "Default")
      (node (ref "U$2") (pin "P9.14") (pinfunction "GPIO_40_P9.14") (pintype "bidirectional"))
    )
    (net (code "125") (name "unconnected-(U$2B-GPIO_48-PadP9.15)") (class "Default")
      (node (ref "U$2") (pin "P9.15") (pinfunction "GPIO_48_P9.15") (pintype "bidirectional"))
    )
    (net (code "126") (name "unconnected-(U$2B-GPIO_49-PadP9.23)") (class "Default")
      (node (ref "U$2") (pin "P9.23") (pinfunction "GPIO_49_P9.23") (pintype "bidirectional"))
    )
    (net (code "127") (name "unconnected-(U$2B-GPIO_51-PadP9.16)") (class "Default")
      (node (ref "U$2") (pin "P9.16") (pinfunction "GPIO_51_P9.16") (pintype "bidirectional"))
    )
    (net (code "128") (name "unconnected-(U$2B-GPIO_60-PadP9.12)") (class "Default")
      (node (ref "U$2") (pin "P9.12") (pinfunction "GPIO_60_P9.12") (pintype "bidirectional"))
    )
    (net (code "129") (name "unconnected-(U$2B-GPIO_117-PadP9.25)") (class "Default")
      (node (ref "U$2") (pin "P9.25") (pinfunction "GPIO_117_P9.25") (pintype "bidirectional"))
    )
    (net (code "130") (name "unconnected-(U$2B-GPIO_125-PadP9.27)") (class "Default")
      (node (ref "U$2") (pin "P9.27") (pinfunction "GPIO_125_P9.27") (pintype "bidirectional"))
    )
    (net (code "131") (name "unconnected-(U$2B-PWR_BUT-PadP9.9)") (class "Default")
      (node (ref "U$2") (pin "P9.9") (pinfunction "PWR_BUT_P9.9") (pintype "bidirectional"))
    )
    (net (code "132") (name "unconnected-(U$2B-SYS_5V-PadP9.7)") (class "Default")
      (node (ref "U$2") (pin "P9.7") (pinfunction "SYS_5V_P9.7") (pintype "bidirectional"))
    )
    (net (code "133") (name "unconnected-(U$2B-SYS_5V-PadP9.8)") (class "Default")
      (node (ref "U$2") (pin "P9.8") (pinfunction "SYS_5V_P9.8") (pintype "bidirectional"))
    )
    (net (code "134") (name "unconnected-(U$2B-VDD_5V-PadP9.5)") (class "Default")
      (node (ref "U$2") (pin "P9.5") (pinfunction "VDD_5V_P9.5") (pintype "bidirectional"))
    )
    (net (code "135") (name "unconnected-(U$2B-VDD_5V-PadP9.6)") (class "Default")
      (node (ref "U$2") (pin "P9.6") (pinfunction "VDD_5V_P9.6") (pintype "bidirectional"))
    )
    (net (code "136") (name "unconnected-(U$2B-VDD_ADC-PadP9.32)") (class "Default")
      (node (ref "U$2") (pin "P9.32") (pinfunction "VDD_ADC_P9.32") (pintype "bidirectional"))
    )
    (net (code "137") (name "unconnected-(U$3-~{INT}-Pad17)") (class "Default")
      (node (ref "U$3") (pin "17") (pinfunction "~{INT}_17") (pintype "output"))
    )
    (net (code "138") (name "unconnected-(U$5-HOLD_~{THRU}-Pad5)") (class "Default")
      (node (ref "U$5") (pin "5") (pinfunction "HOLD_~{THRU}_5") (pintype "bidirectional"))
    )
    (net (code "139") (name "unconnected-(U$5-SHDN-Pad1)") (class "Default")
      (node (ref "U$5") (pin "1") (pinfunction "SHDN_1") (pintype "bidirectional"))
    )
    (net (code "140") (name "unconnected-(U$6-HOLD_~{THRU}-Pad5)") (class "Default")
      (node (ref "U$6") (pin "5") (pinfunction "HOLD_~{THRU}_5") (pintype "bidirectional"))
    )
    (net (code "141") (name "unconnected-(U$6-SHDN-Pad1)") (class "Default")
      (node (ref "U$6") (pin "1") (pinfunction "SHDN_1") (pintype "bidirectional"))
    )
    (net (code "142") (name "unconnected-(U$7-HOLD_~{THRU}-Pad5)") (class "Default")
      (node (ref "U$7") (pin "5") (pinfunction "HOLD_~{THRU}_5") (pintype "bidirectional"))
    )
    (net (code "143") (name "unconnected-(U$7-SHDN-Pad1)") (class "Default")
      (node (ref "U$7") (pin "1") (pinfunction "SHDN_1") (pintype "bidirectional"))
    )
    (net (code "144") (name "unconnected-(U$8-HOLD_~{THRU}-Pad5)") (class "Default")
      (node (ref "U$8") (pin "5") (pinfunction "HOLD_~{THRU}_5") (pintype "bidirectional"))
    )
    (net (code "145") (name "unconnected-(U$8-SHDN-Pad1)") (class "Default")
      (node (ref "U$8") (pin "1") (pinfunction "SHDN_1") (pintype "bidirectional"))
    )
    (net (code "146") (name "unconnected-(U3-DEN_A{slash}G-Pad13)") (class "Default")
      (node (ref "U3") (pin "13") (pinfunction "DEN_A/G_13") (pintype "bidirectional"))
    )
    (net (code "147") (name "unconnected-(U3-DRDY_M-Pad9)") (class "Default")
      (node (ref "U3") (pin "9") (pinfunction "DRDY_M_9") (pintype "bidirectional"))
    )
    (net (code "148") (name "unconnected-(U3-INT1_A{slash}G-Pad11)") (class "Default")
      (node (ref "U3") (pin "11") (pinfunction "INT1_A/G_11") (pintype "bidirectional"))
    )
    (net (code "149") (name "unconnected-(U3-INT2_A{slash}G-Pad12)") (class "Default")
      (node (ref "U3") (pin "12") (pinfunction "INT2_A/G_12") (pintype "bidirectional"))
    )
    (net (code "150") (name "unconnected-(U3-INT_M-Pad10)") (class "Default")
      (node (ref "U3") (pin "10") (pinfunction "INT_M_10") (pintype "bidirectional"))
    )
    (net (code "151") (name "unconnected-(X2-S1-PadS@1)") (class "Default")
      (node (ref "X2") (pin "S@1") (pinfunction "S1_S@1") (pintype "passive"))
    )
    (net (code "152") (name "unconnected-(X2-S2-PadS@2)") (class "Default")
      (node (ref "X2") (pin "S@2") (pinfunction "S2_S@2") (pintype "passive"))
    )
  )
)
